# Group_06.net
KiCad netlist of a schematic drawn in EAGLE
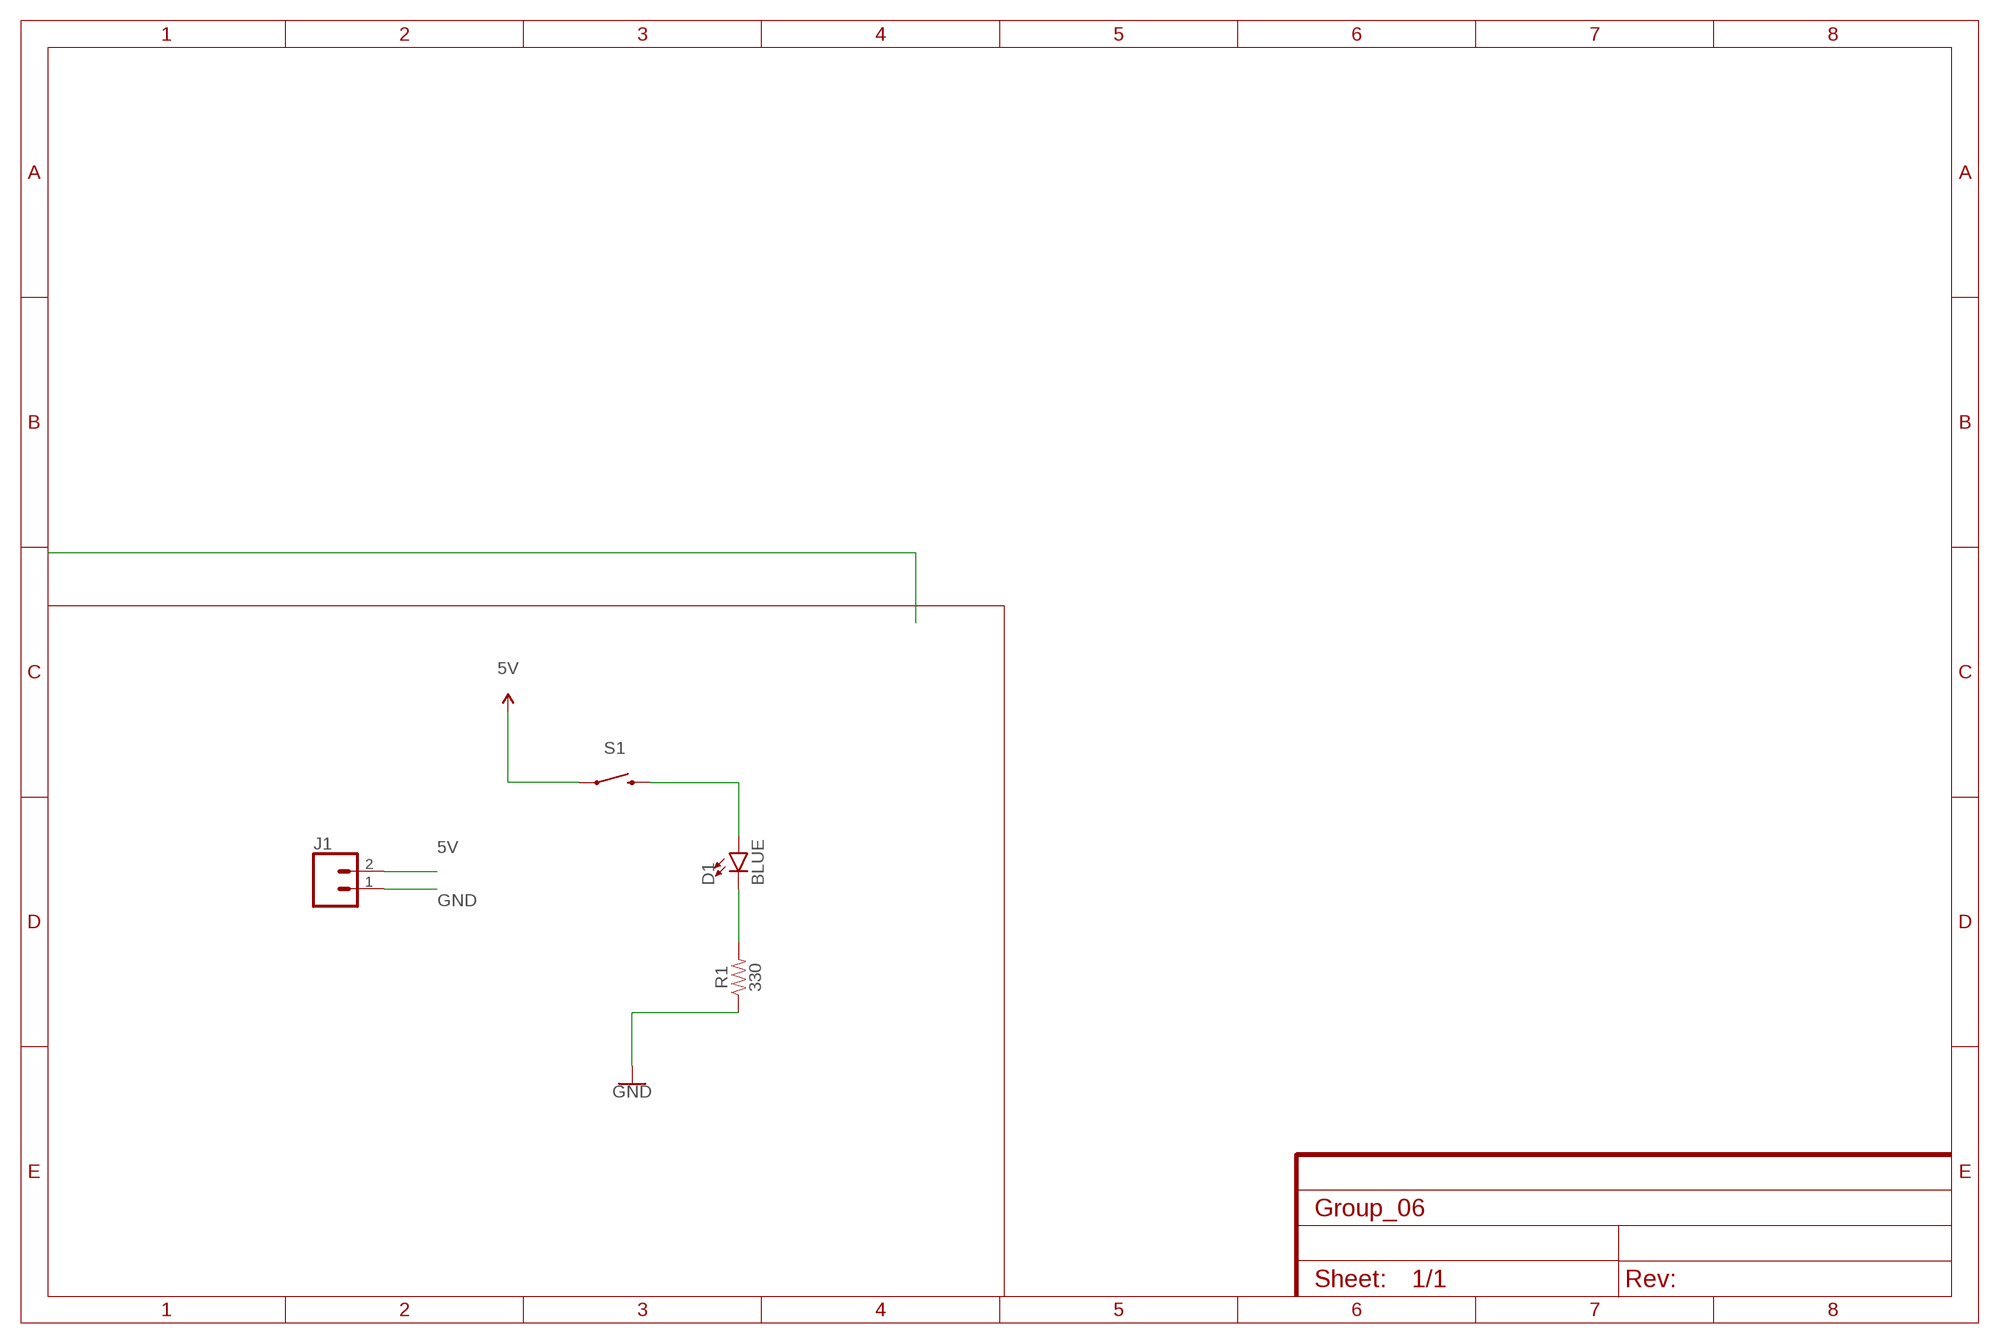
[diagram p0: schematic, sheet 1]

(export (version "E")
  (design (tool "Eeschema 10.0.6"))
  (components
    (comp (ref "D1")
      (value "BLUE")
      (footprint "eagle-import:LED-0603")
      (libsource (lib "eagle-import") (part "LED-BLUE0603"))
    )
    (comp (ref "J1")
      (value "CONN_021X02_NO_SILK")
      (footprint "eagle-import:1X02_NO_SILK")
      (libsource (lib "eagle-import") (part "CONN_021X02_NO_SILK"))
    )
    (comp (ref "R1")
      (value "330")
      (footprint "eagle-import:AXIAL-0.3")
      (libsource (lib "eagle-import") (part "RESISTORAXIAL-0.3"))
    )
    (comp (ref "S1")
      (value "MOMENTARY-SWITCH-SPST-PTH-6.0MM")
      (footprint "eagle-import:TACTILE_SWITCH_PTH_6.0MM")
      (libsource (lib "eagle-import") (part "MOMENTARY-SWITCH-SPST-PTH-6.0MM"))
    )
  )
  (nets
    (net (code "1") (name "5V") (class "Default")
      (node (ref "J1") (pin "2") (pinfunction "2_2") (pintype "passive"))
      (node (ref "S1") (pin "1") (pinfunction "1_1") (pintype "passive"))
    )
    (net (code "2") (name "GND") (class "Default")
      (node (ref "J1") (pin "1") (pinfunction "1_1") (pintype "passive"))
      (node (ref "R1") (pin "P$1") (pinfunction "1_P$1") (pintype "passive"))
    )
    (net (code "3") (name "Net-(R1-2)") (class "Default")
      (node (ref "D1") (pin "C") (pinfunction "C_C") (pintype "passive"))
      (node (ref "R1") (pin "P$2") (pinfunction "2_P$2") (pintype "passive"))
    )
    (net (code "4") (name "Net-(S1-2)") (class "Default")
      (node (ref "D1") (pin "A") (pinfunction "A_A") (pintype "passive"))
      (node (ref "S1") (pin "3") (pinfunction "2_3") (pintype "passive"))
    )
  )
)
